# working.net
KiCad netlist of a schematic drawn in EAGLE
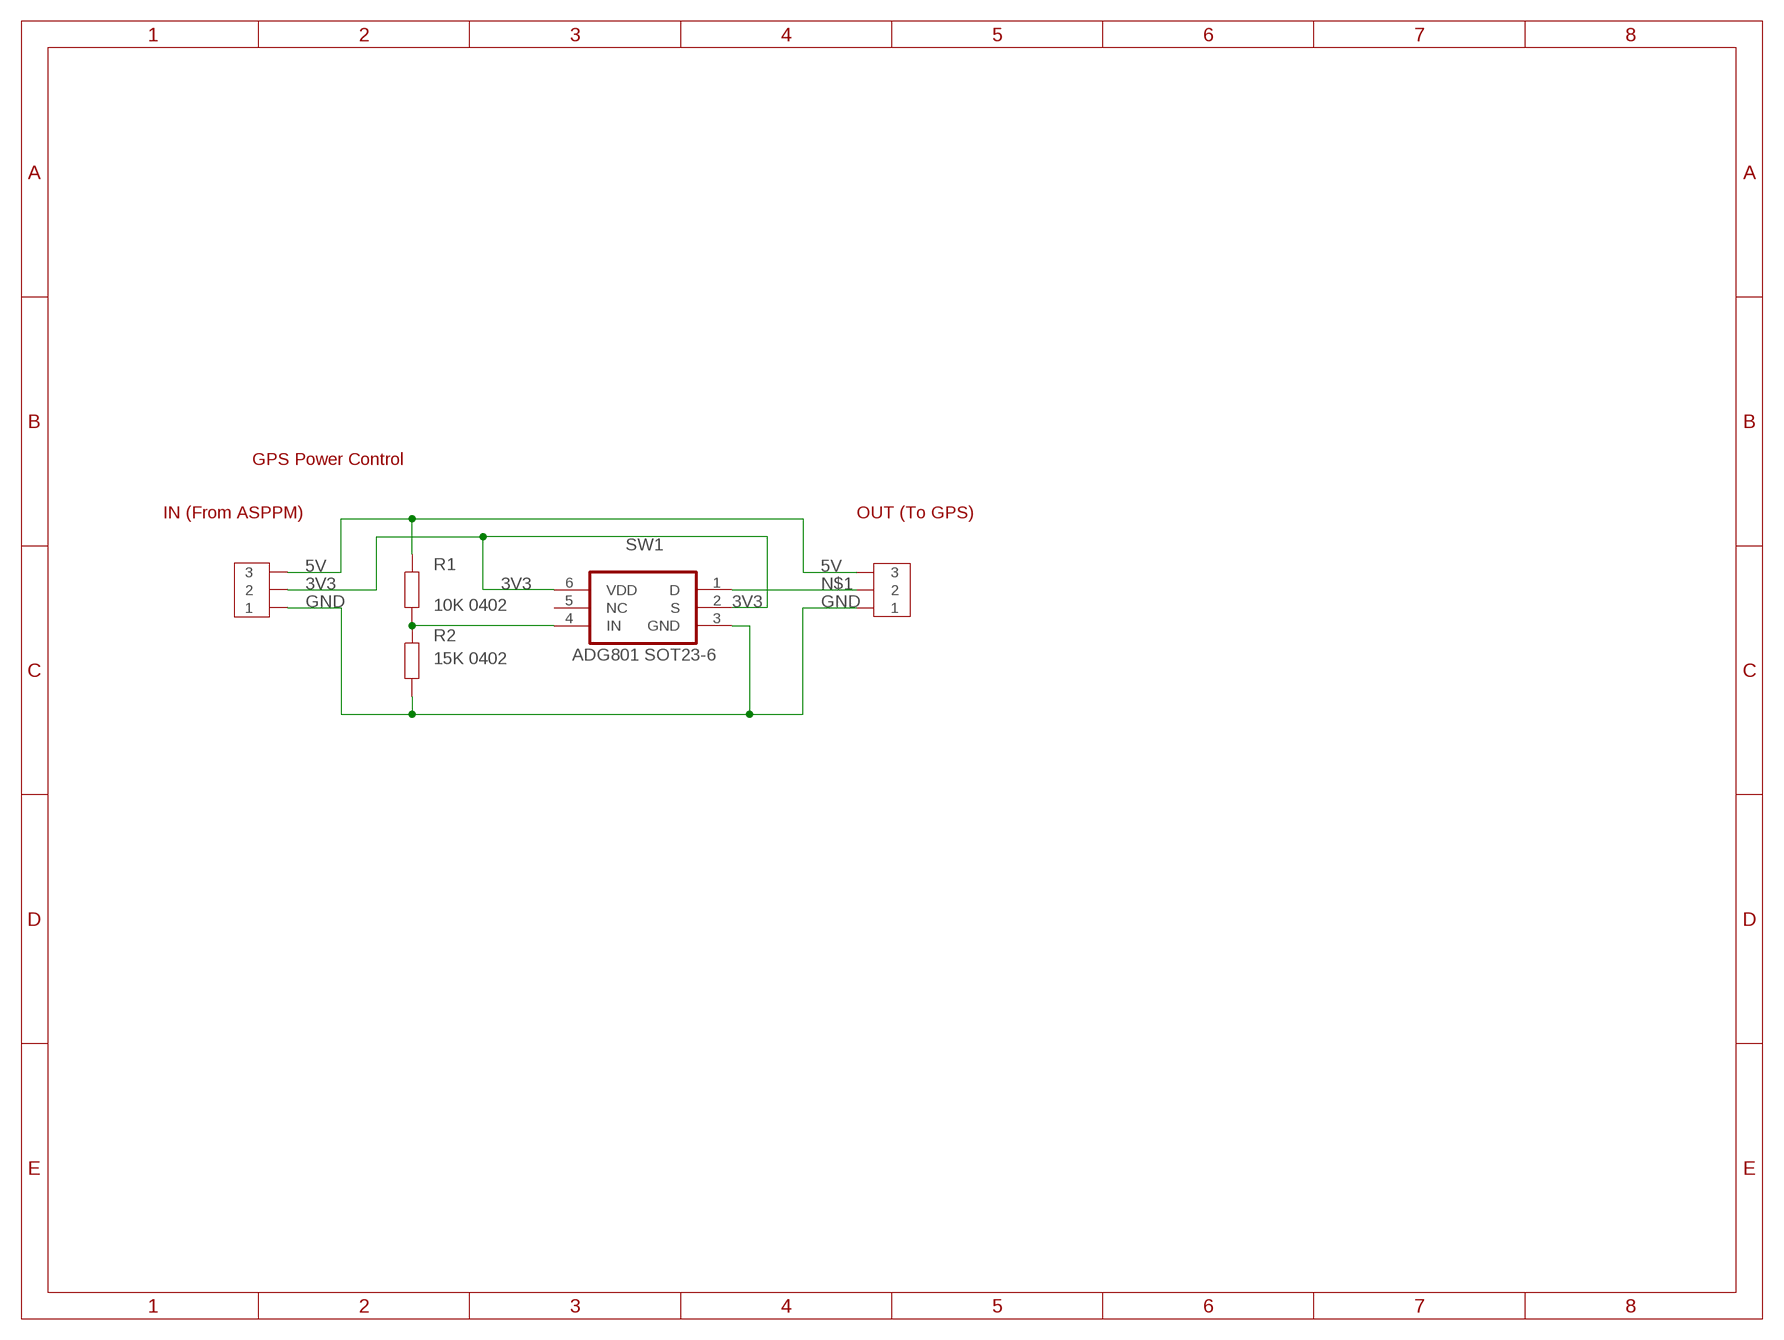
[diagram p0: schematic, sheet 1]

(export (version "E")
  (design (tool "Eeschema 10.0.6"))
  (components
    (comp (ref "JP1")
      (value "3PIN_SMD")
      (footprint "eagle-import:1X3-2MM")
      (libsource (lib "eagle-import") (part "3PIN_SMD"))
    )
    (comp (ref "JP2")
      (value "3PIN_SMD")
      (footprint "eagle-import:1X3-2MM")
      (libsource (lib "eagle-import") (part "3PIN_SMD"))
    )
    (comp (ref "R1")
      (value "10K 0402")
      (footprint "eagle-import:0402")
      (libsource (lib "eagle-import") (part "RESISTOR0402"))
    )
    (comp (ref "R2")
      (value "15K 0402")
      (footprint "eagle-import:0402")
      (libsource (lib "eagle-import") (part "RESISTOR0402"))
    )
    (comp (ref "SW1")
      (value "ADG801 SOT23-6")
      (footprint "eagle-import:SOT23-6")
      (libsource (lib "eagle-import") (part "ADG801SOT23-6"))
    )
  )
  (nets
    (net (code "1") (name "/3V3") (class "Default")
      (node (ref "JP1") (pin "P$2") (pinfunction "2_P$2") (pintype "bidirectional"))
      (node (ref "SW1") (pin "2") (pinfunction "S_2") (pintype "bidirectional"))
      (node (ref "SW1") (pin "6") (pinfunction "VDD_6") (pintype "bidirectional"))
    )
    (net (code "2") (name "/5V") (class "Default")
      (node (ref "JP1") (pin "P$3") (pinfunction "3_P$3") (pintype "bidirectional"))
      (node (ref "JP2") (pin "P$3") (pinfunction "3_P$3") (pintype "bidirectional"))
      (node (ref "R1") (pin "2") (pinfunction "2_2") (pintype "passive"))
    )
    (net (code "3") (name "/GND") (class "Default")
      (node (ref "JP1") (pin "P$1") (pinfunction "1_P$1") (pintype "bidirectional"))
      (node (ref "JP2") (pin "P$1") (pinfunction "1_P$1") (pintype "bidirectional"))
      (node (ref "R2") (pin "1") (pinfunction "1_1") (pintype "passive"))
      (node (ref "SW1") (pin "3") (pinfunction "GND_3") (pintype "bidirectional"))
    )
    (net (code "4") (name "/N$1") (class "Default")
      (node (ref "JP2") (pin "P$2") (pinfunction "2_P$2") (pintype "bidirectional"))
      (node (ref "SW1") (pin "1") (pinfunction "D_1") (pintype "bidirectional"))
    )
    (net (code "5") (name "Net-(SW1-IN)") (class "Default")
      (node (ref "R1") (pin "1") (pinfunction "1_1") (pintype "passive"))
      (node (ref "R2") (pin "2") (pinfunction "2_2") (pintype "passive"))
      (node (ref "SW1") (pin "4") (pinfunction "IN_4") (pintype "bidirectional"))
    )
    (net (code "6") (name "unconnected-(SW1-NC-Pad5)") (class "Default")
      (node (ref "SW1") (pin "5") (pinfunction "NC_5") (pintype "bidirectional"))
    )
  )
)
